# SH.net
KiCad netlist of a schematic drawn in Altium Designer
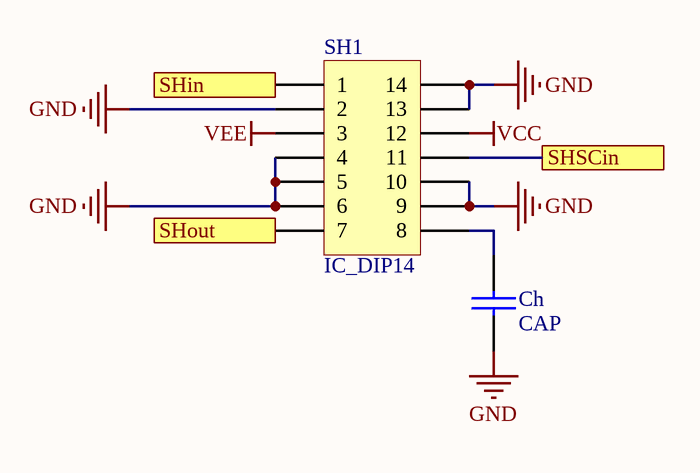
[diagram p0: SH.SchDoc]

(export (version "E")
  (design (tool "Eeschema 10.0.6"))
  (components
    (comp (ref "Ch") (value "CAP") (footprint "1206") (libsource (lib "LIBEBAL") (part "CAP")))
    (comp (ref "SH1") (value "IC_DIP14") (footprint "D014_M") (libsource (lib "LIBEBAL") (part "IC_DIP14")))
  )
  (nets
    (net (code "1") (name "/SHSCin") (class "Default")
      (node (ref "SH1") (pin "11") (pinfunction "11_11") (pintype "passive"))
    )
    (net (code "2") (name "/SHin") (class "Default")
      (node (ref "SH1") (pin "1") (pinfunction "1_1") (pintype "passive"))
    )
    (net (code "3") (name "/SHout") (class "Default")
      (node (ref "SH1") (pin "7") (pinfunction "7_7") (pintype "passive"))
    )
    (net (code "4") (name "GND") (class "Default")
      (node (ref "Ch") (pin "2") (pinfunction "2_2") (pintype "passive"))
      (node (ref "SH1") (pin "10") (pinfunction "10_10") (pintype "passive"))
      (node (ref "SH1") (pin "13") (pinfunction "13_13") (pintype "passive"))
      (node (ref "SH1") (pin "14") (pinfunction "14_14") (pintype "passive"))
      (node (ref "SH1") (pin "2") (pinfunction "2_2") (pintype "passive"))
      (node (ref "SH1") (pin "4") (pinfunction "4_4") (pintype "passive"))
      (node (ref "SH1") (pin "5") (pinfunction "5_5") (pintype "passive"))
      (node (ref "SH1") (pin "6") (pinfunction "6_6") (pintype "passive"))
      (node (ref "SH1") (pin "9") (pinfunction "9_9") (pintype "passive"))
    )
    (net (code "5") (name "Net-(Ch-Pad1)") (class "Default")
      (node (ref "Ch") (pin "1") (pinfunction "1_1") (pintype "passive"))
      (node (ref "SH1") (pin "8") (pinfunction "8_8") (pintype "passive"))
    )
    (net (code "6") (name "VCC") (class "Default")
      (node (ref "SH1") (pin "12") (pinfunction "12_12") (pintype "passive"))
    )
    (net (code "7") (name "VEE") (class "Default")
      (node (ref "SH1") (pin "3") (pinfunction "3_3") (pintype "passive"))
    )
  )
)
